# SheetSCH.net
KiCad netlist of a schematic drawn in Altium Designer
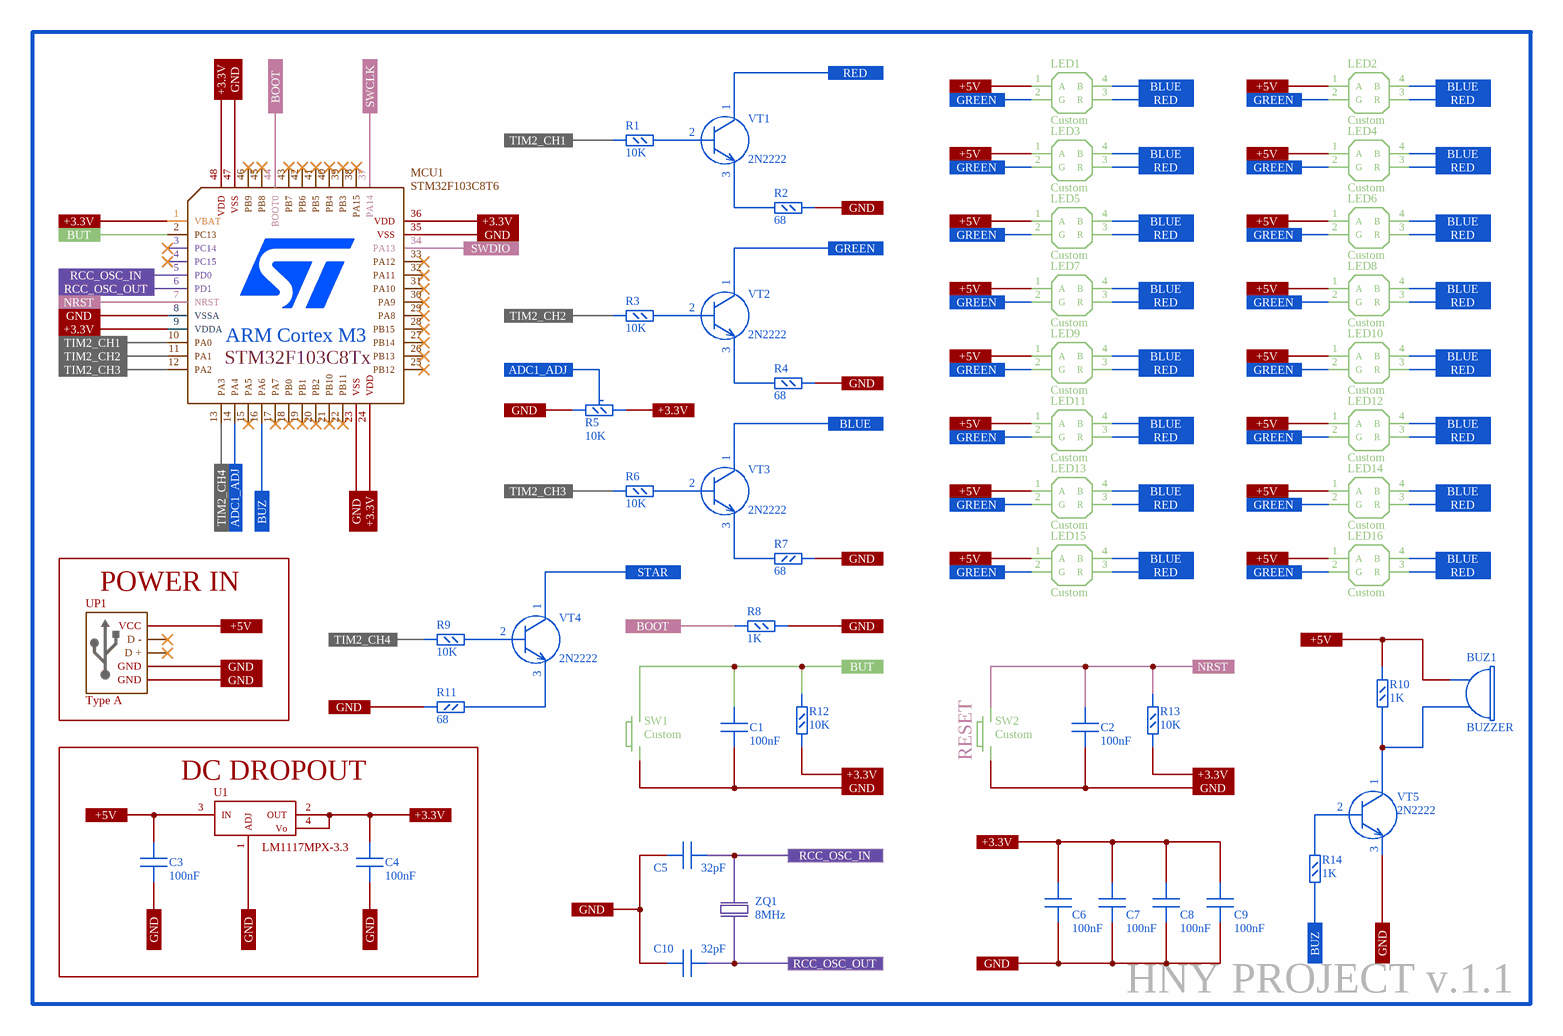
[diagram p0: SheetSCH.SchDoc]

(export (version "E")
  (design (tool "Eeschema 10.0.6"))
  (components
    (comp (ref "BUZ1")
      (value "BUZZER")
      (footprint "BUZZER-5.08MM-D10.5MM")
      (libsource (lib "CommonElements") (part "Buzzer"))
    )
    (comp (ref "C1") (value "100nF") (footprint "C0603") (libsource (lib "CustomMillLib_Col") (part "Cap")))
    (comp (ref "C2") (value "100nF") (footprint "C0603") (libsource (lib "CustomMillLib_Col") (part "Cap")))
    (comp (ref "C3") (value "100nF") (footprint "C0805") (libsource (lib "CustomMillLib_Col") (part "Cap")))
    (comp (ref "C4") (value "100nF") (footprint "C0805") (libsource (lib "CustomMillLib_Col") (part "Cap")))
    (comp (ref "C5") (value "32pF") (footprint "C0603") (libsource (lib "CustomMillLib_Col") (part "Cap")))
    (comp (ref "C6") (value "100nF") (footprint "C0603") (libsource (lib "CustomMillLib_Col") (part "Cap")))
    (comp (ref "C7") (value "100nF") (footprint "C0603") (libsource (lib "CustomMillLib_Col") (part "Cap")))
    (comp (ref "C8") (value "100nF") (footprint "C0603") (libsource (lib "CustomMillLib_Col") (part "Cap")))
    (comp (ref "C9") (value "100nF") (footprint "C0603") (libsource (lib "CustomMillLib_Col") (part "Cap")))
    (comp (ref "C10") (value "32pF") (footprint "C0603") (libsource (lib "CustomMillLib_Col") (part "Cap")))
    (comp (ref "LED1")
      (value "Custom")
      (footprint "LED_RGB_2_LAYERS")
      (libsource (lib "CustomMillLib_Col") (part "LED-RGB"))
    )
    (comp (ref "LED2")
      (value "Custom")
      (footprint "LED_RGB_2_LAYERS")
      (libsource (lib "CustomMillLib_Col") (part "LED-RGB"))
    )
    (comp (ref "LED3")
      (value "Custom")
      (footprint "LED_RGB_2_LAYERS")
      (libsource (lib "CustomMillLib_Col") (part "LED-RGB"))
    )
    (comp (ref "LED4")
      (value "Custom")
      (footprint "LED_RGB_2_LAYERS")
      (libsource (lib "CustomMillLib_Col") (part "LED-RGB"))
    )
    (comp (ref "LED5")
      (value "Custom")
      (footprint "LED_RGB_2_LAYERS")
      (libsource (lib "CustomMillLib_Col") (part "LED-RGB"))
    )
    (comp (ref "LED6")
      (value "Custom")
      (footprint "LED_RGB_2_LAYERS")
      (libsource (lib "CustomMillLib_Col") (part "LED-RGB"))
    )
    (comp (ref "LED7")
      (value "Custom")
      (footprint "LED_RGB_2_LAYERS")
      (libsource (lib "CustomMillLib_Col") (part "LED-RGB"))
    )
    (comp (ref "LED8")
      (value "Custom")
      (footprint "LED_RGB_2_LAYERS")
      (libsource (lib "CustomMillLib_Col") (part "LED-RGB"))
    )
    (comp (ref "LED9")
      (value "Custom")
      (footprint "LED_RGB_2_LAYERS")
      (libsource (lib "CustomMillLib_Col") (part "LED-RGB"))
    )
    (comp (ref "LED10")
      (value "Custom")
      (footprint "LED_RGB_2_LAYERS")
      (libsource (lib "CustomMillLib_Col") (part "LED-RGB"))
    )
    (comp (ref "LED11")
      (value "Custom")
      (footprint "LED_RGB_2_LAYERS")
      (libsource (lib "CustomMillLib_Col") (part "LED-RGB"))
    )
    (comp (ref "LED12")
      (value "Custom")
      (footprint "LED_RGB_2_LAYERS")
      (libsource (lib "CustomMillLib_Col") (part "LED-RGB"))
    )
    (comp (ref "LED13")
      (value "Custom")
      (footprint "LED_RGB_2_LAYERS")
      (libsource (lib "CustomMillLib_Col") (part "LED-RGB"))
    )
    (comp (ref "LED14")
      (value "Custom")
      (footprint "LED_RGB_2_LAYERS")
      (libsource (lib "CustomMillLib_Col") (part "LED-RGB"))
    )
    (comp (ref "LED15")
      (value "Custom")
      (footprint "LED_RGB_2_LAYERS")
      (libsource (lib "CustomMillLib_Col") (part "LED-RGB"))
    )
    (comp (ref "LED16")
      (value "Custom")
      (footprint "LED_RGB_2_LAYERS")
      (libsource (lib "CustomMillLib_Col") (part "LED-RGB"))
    )
    (comp (ref "MCU1")
      (value "STM32F103C8T6")
      (footprint "LQFP48")
      (libsource (lib "STM32") (part "STM32F103C8Tx"))
    )
    (comp (ref "R1") (value "10K") (footprint "R0603") (libsource (lib "CustomMillLib_Col") (part "Res")))
    (comp (ref "R2") (value "68") (footprint "R1206") (libsource (lib "CustomMillLib_Col") (part "Res")))
    (comp (ref "R3") (value "10K") (footprint "R0603") (libsource (lib "CustomMillLib_Col") (part "Res")))
    (comp (ref "R4") (value "68") (footprint "R1206") (libsource (lib "CustomMillLib_Col") (part "Res")))
    (comp (ref "R5") (value "10K") (footprint "EVM3") (libsource (lib "CustomMillLib_Col") (part "Res Adj")))
    (comp (ref "R6") (value "10K") (footprint "R0603") (libsource (lib "CustomMillLib_Col") (part "Res")))
    (comp (ref "R7") (value "68") (footprint "R1206") (libsource (lib "CustomMillLib_Col") (part "Res")))
    (comp (ref "R8") (value "1K") (footprint "R0603") (libsource (lib "CustomMillLib_Col") (part "Res")))
    (comp (ref "R9") (value "10K") (footprint "R0603") (libsource (lib "CustomMillLib_Col") (part "Res")))
    (comp (ref "R10") (value "1K") (footprint "R0603") (libsource (lib "CustomMillLib_Col") (part "Res")))
    (comp (ref "R11") (value "68") (footprint "R1206") (libsource (lib "CustomMillLib_Col") (part "Res")))
    (comp (ref "R12") (value "10K") (footprint "R0603") (libsource (lib "CustomMillLib_Col") (part "Res")))
    (comp (ref "R13") (value "10K") (footprint "R0603") (libsource (lib "CustomMillLib_Col") (part "Res")))
    (comp (ref "R14") (value "1K") (footprint "R0603") (libsource (lib "CustomMillLib_Col") (part "Res")))
    (comp (ref "SW1")
      (value "Custom")
      (footprint "BUT-6.5X4.5MM")
      (libsource (lib "CommonElements") (part "Button"))
    )
    (comp (ref "SW2")
      (value "Custom")
      (footprint "BUT-6.5X4.5MM")
      (libsource (lib "CommonElements") (part "Button"))
    )
    (comp (ref "U1")
      (value "LM1117MPX-3.3")
      (footprint "SOT-223")
      (libsource (lib "PowerSupplies_Col") (part "LM1117"))
    )
    (comp (ref "UP1") (value "Type A") (footprint "USB-MICRO-F") (libsource (lib "Connectors") (part "USB")))
    (comp (ref "VT1")
      (value "2N2222")
      (footprint "SOT-23-123")
      (libsource (lib "CommonElements") (part "NPN_CBE"))
    )
    (comp (ref "VT2")
      (value "2N2222")
      (footprint "SOT-23-123")
      (libsource (lib "CommonElements") (part "NPN_CBE"))
    )
    (comp (ref "VT3")
      (value "2N2222")
      (footprint "SOT-23-123")
      (libsource (lib "CommonElements") (part "NPN_CBE"))
    )
    (comp (ref "VT4")
      (value "2N2222")
      (footprint "SOT-23-123")
      (libsource (lib "CommonElements") (part "NPN_CBE"))
    )
    (comp (ref "VT5")
      (value "2N2222")
      (footprint "SOT-23-123")
      (libsource (lib "CommonElements") (part "NPN_CBE"))
    )
    (comp (ref "ZQ1")
      (value "8MHz")
      (footprint "HC-49")
      (libsource (lib "CustomMillLib_Col") (part "Crystall"))
    )
  )
  (nets
    (net (code "1") (name "/+3.3V") (class "Default")
      (node (ref "C4") (pin "2") (pinfunction "62_2") (pintype "passive"))
      (node (ref "C6") (pin "2") (pinfunction "62_2") (pintype "passive"))
      (node (ref "C7") (pin "2") (pinfunction "62_2") (pintype "passive"))
      (node (ref "C8") (pin "2") (pinfunction "62_2") (pintype "passive"))
      (node (ref "C9") (pin "2") (pinfunction "62_2") (pintype "passive"))
      (node (ref "MCU1") (pin "1") (pinfunction "VBAT_1") (pintype "passive"))
      (node (ref "MCU1") (pin "24") (pinfunction "VDD_24") (pintype "passive"))
      (node (ref "MCU1") (pin "36") (pinfunction "VDD_36") (pintype "passive"))
      (node (ref "MCU1") (pin "48") (pinfunction "VDD_48") (pintype "passive"))
      (node (ref "MCU1") (pin "9") (pinfunction "VDDA_9") (pintype "passive"))
      (node (ref "R12") (pin "2") (pinfunction "2_2") (pintype "passive"))
      (node (ref "R13") (pin "2") (pinfunction "2_2") (pintype "passive"))
      (node (ref "R5") (pin "3") (pinfunction "2_3") (pintype "passive"))
      (node (ref "U1") (pin "2") (pinfunction "OUT_2") (pintype "passive"))
      (node (ref "U1") (pin "4") (pinfunction "Vo_4") (pintype "passive"))
    )
    (net (code "2") (name "/+5V") (class "Default")
      (node (ref "BUZ1") (pin "1") (pintype "passive"))
      (node (ref "C3") (pin "2") (pinfunction "62_2") (pintype "passive"))
      (node (ref "LED1") (pin "1") (pinfunction "A_1") (pintype "passive"))
      (node (ref "LED10") (pin "1") (pinfunction "A_1") (pintype "passive"))
      (node (ref "LED11") (pin "1") (pinfunction "A_1") (pintype "passive"))
      (node (ref "LED12") (pin "1") (pinfunction "A_1") (pintype "passive"))
      (node (ref "LED13") (pin "1") (pinfunction "A_1") (pintype "passive"))
      (node (ref "LED14") (pin "1") (pinfunction "A_1") (pintype "passive"))
      (node (ref "LED15") (pin "1") (pinfunction "A_1") (pintype "passive"))
      (node (ref "LED16") (pin "1") (pinfunction "A_1") (pintype "passive"))
      (node (ref "LED2") (pin "1") (pinfunction "A_1") (pintype "passive"))
      (node (ref "LED3") (pin "1") (pinfunction "A_1") (pintype "passive"))
      (node (ref "LED4") (pin "1") (pinfunction "A_1") (pintype "passive"))
      (node (ref "LED5") (pin "1") (pinfunction "A_1") (pintype "passive"))
      (node (ref "LED6") (pin "1") (pinfunction "A_1") (pintype "passive"))
      (node (ref "LED7") (pin "1") (pinfunction "A_1") (pintype "passive"))
      (node (ref "LED8") (pin "1") (pinfunction "A_1") (pintype "passive"))
      (node (ref "LED9") (pin "1") (pinfunction "A_1") (pintype "passive"))
      (node (ref "R10") (pin "1") (pinfunction "2_1") (pintype "passive"))
      (node (ref "U1") (pin "3") (pinfunction "IN_3") (pintype "passive"))
      (node (ref "UP1") (pin "1") (pinfunction "VCC_1") (pintype "passive"))
    )
    (net (code "3") (name "/ADC1_ADJ") (class "Default")
      (node (ref "MCU1") (pin "14") (pinfunction "PA4_14") (pintype "passive"))
      (node (ref "R5") (pin "2") (pintype "passive"))
    )
    (net (code "4") (name "/BLUE") (class "Default")
      (node (ref "LED1") (pin "4") (pinfunction "B_4") (pintype "passive"))
      (node (ref "LED10") (pin "4") (pinfunction "B_4") (pintype "passive"))
      (node (ref "LED11") (pin "4") (pinfunction "B_4") (pintype "passive"))
      (node (ref "LED12") (pin "4") (pinfunction "B_4") (pintype "passive"))
      (node (ref "LED13") (pin "4") (pinfunction "B_4") (pintype "passive"))
      (node (ref "LED14") (pin "4") (pinfunction "B_4") (pintype "passive"))
      (node (ref "LED15") (pin "4") (pinfunction "B_4") (pintype "passive"))
      (node (ref "LED16") (pin "4") (pinfunction "B_4") (pintype "passive"))
      (node (ref "LED2") (pin "4") (pinfunction "B_4") (pintype "passive"))
      (node (ref "LED3") (pin "4") (pinfunction "B_4") (pintype "passive"))
      (node (ref "LED4") (pin "4") (pinfunction "B_4") (pintype "passive"))
      (node (ref "LED5") (pin "4") (pinfunction "B_4") (pintype "passive"))
      (node (ref "LED6") (pin "4") (pinfunction "B_4") (pintype "passive"))
      (node (ref "LED7") (pin "4") (pinfunction "B_4") (pintype "passive"))
      (node (ref "LED8") (pin "4") (pinfunction "B_4") (pintype "passive"))
      (node (ref "LED9") (pin "4") (pinfunction "B_4") (pintype "passive"))
      (node (ref "VT3") (pin "1") (pintype "passive"))
    )
    (net (code "5") (name "/BOOT") (class "Default")
      (node (ref "MCU1") (pin "44") (pinfunction "BOOT0_44") (pintype "passive"))
      (node (ref "R8") (pin "1") (pinfunction "2_1") (pintype "passive"))
    )
    (net (code "6") (name "/BUT") (class "Default")
      (node (ref "C1") (pin "2") (pinfunction "62_2") (pintype "passive"))
      (node (ref "MCU1") (pin "2") (pinfunction "PC13_2") (pintype "passive"))
      (node (ref "R12") (pin "1") (pinfunction "2_1") (pintype "passive"))
      (node (ref "SW1") (pin "3") (pinfunction "Q2_3") (pintype "passive"))
    )
    (net (code "7") (name "/BUZ") (class "Default")
      (node (ref "MCU1") (pin "16") (pinfunction "PA6_16") (pintype "passive"))
      (node (ref "R14") (pin "1") (pinfunction "2_1") (pintype "passive"))
    )
    (net (code "8") (name "/GND") (class "Default")
      (node (ref "C1") (pin "1") (pinfunction "61_1") (pintype "passive"))
      (node (ref "C10") (pin "2") (pinfunction "62_2") (pintype "passive"))
      (node (ref "C2") (pin "1") (pinfunction "61_1") (pintype "passive"))
      (node (ref "C3") (pin "1") (pinfunction "61_1") (pintype "passive"))
      (node (ref "C4") (pin "1") (pinfunction "61_1") (pintype "passive"))
      (node (ref "C5") (pin "2") (pinfunction "62_2") (pintype "passive"))
      (node (ref "C6") (pin "1") (pinfunction "61_1") (pintype "passive"))
      (node (ref "C7") (pin "1") (pinfunction "61_1") (pintype "passive"))
      (node (ref "C8") (pin "1") (pinfunction "61_1") (pintype "passive"))
      (node (ref "C9") (pin "1") (pinfunction "61_1") (pintype "passive"))
      (node (ref "MCU1") (pin "23") (pinfunction "VSS_23") (pintype "passive"))
      (node (ref "MCU1") (pin "35") (pinfunction "VSS_35") (pintype "passive"))
      (node (ref "MCU1") (pin "47") (pinfunction "VSS_47") (pintype "passive"))
      (node (ref "MCU1") (pin "8") (pinfunction "VSSA_8") (pintype "passive"))
      (node (ref "R11") (pin "2") (pinfunction "2_2") (pintype "passive"))
      (node (ref "R2") (pin "2") (pinfunction "2_2") (pintype "passive"))
      (node (ref "R4") (pin "2") (pinfunction "2_2") (pintype "passive"))
      (node (ref "R5") (pin "1") (pinfunction "2_1") (pintype "passive"))
      (node (ref "R7") (pin "2") (pinfunction "2_2") (pintype "passive"))
      (node (ref "R8") (pin "2") (pinfunction "2_2") (pintype "passive"))
      (node (ref "SW1") (pin "1") (pinfunction "Q1_1") (pintype "passive"))
      (node (ref "SW2") (pin "1") (pinfunction "Q1_1") (pintype "passive"))
      (node (ref "U1") (pin "1") (pinfunction "ADJ_1") (pintype "passive"))
      (node (ref "UP1") (pin "4") (pinfunction "GND_4") (pintype "passive"))
      (node (ref "UP1") (pin "5") (pinfunction "GND_5") (pintype "passive"))
      (node (ref "VT5") (pin "3") (pintype "passive"))
    )
    (net (code "9") (name "/GREEN") (class "Default")
      (node (ref "LED1") (pin "2") (pinfunction "G_2") (pintype "passive"))
      (node (ref "LED10") (pin "2") (pinfunction "G_2") (pintype "passive"))
      (node (ref "LED11") (pin "2") (pinfunction "G_2") (pintype "passive"))
      (node (ref "LED12") (pin "2") (pinfunction "G_2") (pintype "passive"))
      (node (ref "LED13") (pin "2") (pinfunction "G_2") (pintype "passive"))
      (node (ref "LED14") (pin "2") (pinfunction "G_2") (pintype "passive"))
      (node (ref "LED15") (pin "2") (pinfunction "G_2") (pintype "passive"))
      (node (ref "LED16") (pin "2") (pinfunction "G_2") (pintype "passive"))
      (node (ref "LED2") (pin "2") (pinfunction "G_2") (pintype "passive"))
      (node (ref "LED3") (pin "2") (pinfunction "G_2") (pintype "passive"))
      (node (ref "LED4") (pin "2") (pinfunction "G_2") (pintype "passive"))
      (node (ref "LED5") (pin "2") (pinfunction "G_2") (pintype "passive"))
      (node (ref "LED6") (pin "2") (pinfunction "G_2") (pintype "passive"))
      (node (ref "LED7") (pin "2") (pinfunction "G_2") (pintype "passive"))
      (node (ref "LED8") (pin "2") (pinfunction "G_2") (pintype "passive"))
      (node (ref "LED9") (pin "2") (pinfunction "G_2") (pintype "passive"))
      (node (ref "VT2") (pin "1") (pintype "passive"))
    )
    (net (code "10") (name "/NRST") (class "Default")
      (node (ref "C2") (pin "2") (pinfunction "62_2") (pintype "passive"))
      (node (ref "MCU1") (pin "7") (pinfunction "NRST_7") (pintype "passive"))
      (node (ref "R13") (pin "1") (pinfunction "2_1") (pintype "passive"))
      (node (ref "SW2") (pin "3") (pinfunction "Q2_3") (pintype "passive"))
    )
    (net (code "11") (name "/RCC_OSC_IN") (class "Default")
      (node (ref "C5") (pin "1") (pinfunction "61_1") (pintype "passive"))
      (node (ref "MCU1") (pin "5") (pinfunction "PD0_5") (pintype "passive"))
      (node (ref "ZQ1") (pin "1") (pinfunction "10_1") (pintype "passive"))
    )
    (net (code "12") (name "/RCC_OSC_OUT") (class "Default")
      (node (ref "C10") (pin "1") (pinfunction "61_1") (pintype "passive"))
      (node (ref "MCU1") (pin "6") (pinfunction "PD1_6") (pintype "passive"))
      (node (ref "ZQ1") (pin "2") (pinfunction "2_2") (pintype "passive"))
    )
    (net (code "13") (name "/RED") (class "Default")
      (node (ref "LED1") (pin "3") (pinfunction "R_3") (pintype "passive"))
      (node (ref "LED10") (pin "3") (pinfunction "R_3") (pintype "passive"))
      (node (ref "LED11") (pin "3") (pinfunction "R_3") (pintype "passive"))
      (node (ref "LED12") (pin "3") (pinfunction "R_3") (pintype "passive"))
      (node (ref "LED13") (pin "3") (pinfunction "R_3") (pintype "passive"))
      (node (ref "LED14") (pin "3") (pinfunction "R_3") (pintype "passive"))
      (node (ref "LED15") (pin "3") (pinfunction "R_3") (pintype "passive"))
      (node (ref "LED16") (pin "3") (pinfunction "R_3") (pintype "passive"))
      (node (ref "LED2") (pin "3") (pinfunction "R_3") (pintype "passive"))
      (node (ref "LED3") (pin "3") (pinfunction "R_3") (pintype "passive"))
      (node (ref "LED4") (pin "3") (pinfunction "R_3") (pintype "passive"))
      (node (ref "LED5") (pin "3") (pinfunction "R_3") (pintype "passive"))
      (node (ref "LED6") (pin "3") (pinfunction "R_3") (pintype "passive"))
      (node (ref "LED7") (pin "3") (pinfunction "R_3") (pintype "passive"))
      (node (ref "LED8") (pin "3") (pinfunction "R_3") (pintype "passive"))
      (node (ref "LED9") (pin "3") (pinfunction "R_3") (pintype "passive"))
      (node (ref "VT1") (pin "1") (pintype "passive"))
    )
    (net (code "14") (name "/STAR") (class "Default") (node (ref "VT4") (pin "1") (pintype "passive")))
    (net (code "15") (name "/SWCLK") (class "Default")
      (node (ref "MCU1") (pin "37") (pinfunction "PA14_37") (pintype "passive"))
    )
    (net (code "16") (name "/SWDIO") (class "Default")
      (node (ref "MCU1") (pin "34") (pinfunction "PA13_34") (pintype "passive"))
    )
    (net (code "17") (name "/TIM2_CH1") (class "Default")
      (node (ref "MCU1") (pin "10") (pinfunction "PA0_10") (pintype "passive"))
      (node (ref "R1") (pin "1") (pinfunction "2_1") (pintype "passive"))
    )
    (net (code "18") (name "/TIM2_CH2") (class "Default")
      (node (ref "MCU1") (pin "11") (pinfunction "PA1_11") (pintype "passive"))
      (node (ref "R3") (pin "1") (pinfunction "2_1") (pintype "passive"))
    )
    (net (code "19") (name "/TIM2_CH3") (class "Default")
      (node (ref "MCU1") (pin "12") (pinfunction "PA2_12") (pintype "passive"))
      (node (ref "R6") (pin "1") (pinfunction "2_1") (pintype "passive"))
    )
    (net (code "20") (name "/TIM2_CH4") (class "Default")
      (node (ref "MCU1") (pin "13") (pinfunction "PA3_13") (pintype "passive"))
      (node (ref "R9") (pin "1") (pinfunction "2_1") (pintype "passive"))
    )
    (net (code "21") (name "Net-(BUZ1-Pad2)") (class "Default")
      (node (ref "BUZ1") (pin "2") (pintype "passive"))
      (node (ref "R10") (pin "2") (pinfunction "2_2") (pintype "passive"))
      (node (ref "VT5") (pin "1") (pintype "passive"))
    )
    (net (code "22") (name "Net-(R1-Pad2)") (class "Default")
      (node (ref "R1") (pin "2") (pinfunction "2_2") (pintype "passive"))
      (node (ref "VT1") (pin "2") (pintype "passive"))
    )
    (net (code "23") (name "Net-(R2-2-Pad1)") (class "Default")
      (node (ref "R2") (pin "1") (pinfunction "2_1") (pintype "passive"))
      (node (ref "VT1") (pin "3") (pintype "passive"))
    )
    (net (code "24") (name "Net-(R3-Pad2)") (class "Default")
      (node (ref "R3") (pin "2") (pinfunction "2_2") (pintype "passive"))
      (node (ref "VT2") (pin "2") (pintype "passive"))
    )
    (net (code "25") (name "Net-(R4-2-Pad1)") (class "Default")
      (node (ref "R4") (pin "1") (pinfunction "2_1") (pintype "passive"))
      (node (ref "VT2") (pin "3") (pintype "passive"))
    )
    (net (code "26") (name "Net-(R6-Pad2)") (class "Default")
      (node (ref "R6") (pin "2") (pinfunction "2_2") (pintype "passive"))
      (node (ref "VT3") (pin "2") (pintype "passive"))
    )
    (net (code "27") (name "Net-(R7-2-Pad1)") (class "Default")
      (node (ref "R7") (pin "1") (pinfunction "2_1") (pintype "passive"))
      (node (ref "VT3") (pin "3") (pintype "passive"))
    )
    (net (code "28") (name "Net-(R9-Pad2)") (class "Default")
      (node (ref "R9") (pin "2") (pinfunction "2_2") (pintype "passive"))
      (node (ref "VT4") (pin "2") (pintype "passive"))
    )
    (net (code "29") (name "Net-(R11-2-Pad1)") (class "Default")
      (node (ref "R11") (pin "1") (pinfunction "2_1") (pintype "passive"))
      (node (ref "VT4") (pin "3") (pintype "passive"))
    )
    (net (code "30") (name "Net-(R14-Pad2)") (class "Default")
      (node (ref "R14") (pin "2") (pinfunction "2_2") (pintype "passive"))
      (node (ref "VT5") (pin "2") (pintype "passive"))
    )
    (net (code "31") (name "unconnected-(MCU1-PA5-Pad15)") (class "Default")
      (node (ref "MCU1") (pin "15") (pinfunction "PA5_15") (pintype "passive+no_connect"))
    )
    (net (code "32") (name "unconnected-(MCU1-PA7-Pad17)") (class "Default")
      (node (ref "MCU1") (pin "17") (pinfunction "PA7_17") (pintype "passive+no_connect"))
    )
    (net (code "33") (name "unconnected-(MCU1-PA8-Pad29)") (class "Default")
      (node (ref "MCU1") (pin "29") (pinfunction "PA8_29") (pintype "passive+no_connect"))
    )
    (net (code "34") (name "unconnected-(MCU1-PA9-Pad30)") (class "Default")
      (node (ref "MCU1") (pin "30") (pinfunction "PA9_30") (pintype "passive+no_connect"))
    )
    (net (code "35") (name "unconnected-(MCU1-PA10-Pad31)") (class "Default")
      (node (ref "MCU1") (pin "31") (pinfunction "PA10_31") (pintype "passive+no_connect"))
    )
    (net (code "36") (name "unconnected-(MCU1-PA11-Pad32)") (class "Default")
      (node (ref "MCU1") (pin "32") (pinfunction "PA11_32") (pintype "passive+no_connect"))
    )
    (net (code "37") (name "unconnected-(MCU1-PA12-Pad33)") (class "Default")
      (node (ref "MCU1") (pin "33") (pinfunction "PA12_33") (pintype "passive+no_connect"))
    )
    (net (code "38") (name "unconnected-(MCU1-PA15-Pad38)") (class "Default")
      (node (ref "MCU1") (pin "38") (pinfunction "PA15_38") (pintype "passive+no_connect"))
    )
    (net (code "39") (name "unconnected-(MCU1-PB0-Pad18)") (class "Default")
      (node (ref "MCU1") (pin "18") (pinfunction "PB0_18") (pintype "passive+no_connect"))
    )
    (net (code "40") (name "unconnected-(MCU1-PB1-Pad19)") (class "Default")
      (node (ref "MCU1") (pin "19") (pinfunction "PB1_19") (pintype "passive+no_connect"))
    )
    (net (code "41") (name "unconnected-(MCU1-PB2-Pad20)") (class "Default")
      (node (ref "MCU1") (pin "20") (pinfunction "PB2_20") (pintype "passive+no_connect"))
    )
    (net (code "42") (name "unconnected-(MCU1-PB3-Pad39)") (class "Default")
      (node (ref "MCU1") (pin "39") (pinfunction "PB3_39") (pintype "passive+no_connect"))
    )
    (net (code "43") (name "unconnected-(MCU1-PB4-Pad40)") (class "Default")
      (node (ref "MCU1") (pin "40") (pinfunction "PB4_40") (pintype "passive+no_connect"))
    )
    (net (code "44") (name "unconnected-(MCU1-PB5-Pad41)") (class "Default")
      (node (ref "MCU1") (pin "41") (pinfunction "PB5_41") (pintype "passive+no_connect"))
    )
    (net (code "45") (name "unconnected-(MCU1-PB6-Pad42)") (class "Default")
      (node (ref "MCU1") (pin "42") (pinfunction "PB6_42") (pintype "passive+no_connect"))
    )
    (net (code "46") (name "unconnected-(MCU1-PB7-Pad43)") (class "Default")
      (node (ref "MCU1") (pin "43") (pinfunction "PB7_43") (pintype "passive+no_connect"))
    )
    (net (code "47") (name "unconnected-(MCU1-PB8-Pad45)") (class "Default")
      (node (ref "MCU1") (pin "45") (pinfunction "PB8_45") (pintype "passive+no_connect"))
    )
    (net (code "48") (name "unconnected-(MCU1-PB9-Pad46)") (class "Default")
      (node (ref "MCU1") (pin "46") (pinfunction "PB9_46") (pintype "passive+no_connect"))
    )
    (net (code "49") (name "unconnected-(MCU1-PB10-Pad21)") (class "Default")
      (node (ref "MCU1") (pin "21") (pinfunction "PB10_21") (pintype "passive+no_connect"))
    )
    (net (code "50") (name "unconnected-(MCU1-PB11-Pad22)") (class "Default")
      (node (ref "MCU1") (pin "22") (pinfunction "PB11_22") (pintype "passive+no_connect"))
    )
    (net (code "51") (name "unconnected-(MCU1-PB12-Pad25)") (class "Default")
      (node (ref "MCU1") (pin "25") (pinfunction "PB12_25") (pintype "passive+no_connect"))
    )
    (net (code "52") (name "unconnected-(MCU1-PB13-Pad26)") (class "Default")
      (node (ref "MCU1") (pin "26") (pinfunction "PB13_26") (pintype "passive+no_connect"))
    )
    (net (code "53") (name "unconnected-(MCU1-PB14-Pad27)") (class "Default")
      (node (ref "MCU1") (pin "27") (pinfunction "PB14_27") (pintype "passive+no_connect"))
    )
    (net (code "54") (name "unconnected-(MCU1-PB15-Pad28)") (class "Default")
      (node (ref "MCU1") (pin "28") (pinfunction "PB15_28") (pintype "passive+no_connect"))
    )
    (net (code "55") (name "unconnected-(MCU1-PC14-Pad3)") (class "Default")
      (node (ref "MCU1") (pin "3") (pinfunction "PC14_3") (pintype "passive+no_connect"))
    )
    (net (code "56") (name "unconnected-(MCU1-PC15-Pad4)") (class "Default")
      (node (ref "MCU1") (pin "4") (pinfunction "PC15_4") (pintype "passive+no_connect"))
    )
    (net (code "57") (name "unconnected-(SW1-Q1-Pad2)") (class "Default")
      (node (ref "SW1") (pin "2") (pinfunction "Q1_2") (pintype "passive"))
    )
    (net (code "58") (name "unconnected-(SW1-Q2-Pad4)") (class "Default")
      (node (ref "SW1") (pin "4") (pinfunction "Q2_4") (pintype "passive"))
    )
    (net (code "59") (name "unconnected-(SW2-Q1-Pad2)") (class "Default")
      (node (ref "SW2") (pin "2") (pinfunction "Q1_2") (pintype "passive"))
    )
    (net (code "60") (name "unconnected-(SW2-Q2-Pad4)") (class "Default")
      (node (ref "SW2") (pin "4") (pinfunction "Q2_4") (pintype "passive"))
    )
    (net (code "61") (name "unconnected-(UP1-D_+-Pad3)") (class "Default")
      (node (ref "UP1") (pin "3") (pinfunction "D_+_3") (pintype "passive+no_connect"))
    )
    (net (code "62") (name "unconnected-(UP1-D_--Pad2)") (class "Default")
      (node (ref "UP1") (pin "2") (pinfunction "D_-_2") (pintype "passive+no_connect"))
    )
  )
)
